# BlinkingLightsW555.net
KiCad netlist of a schematic drawn in EAGLE
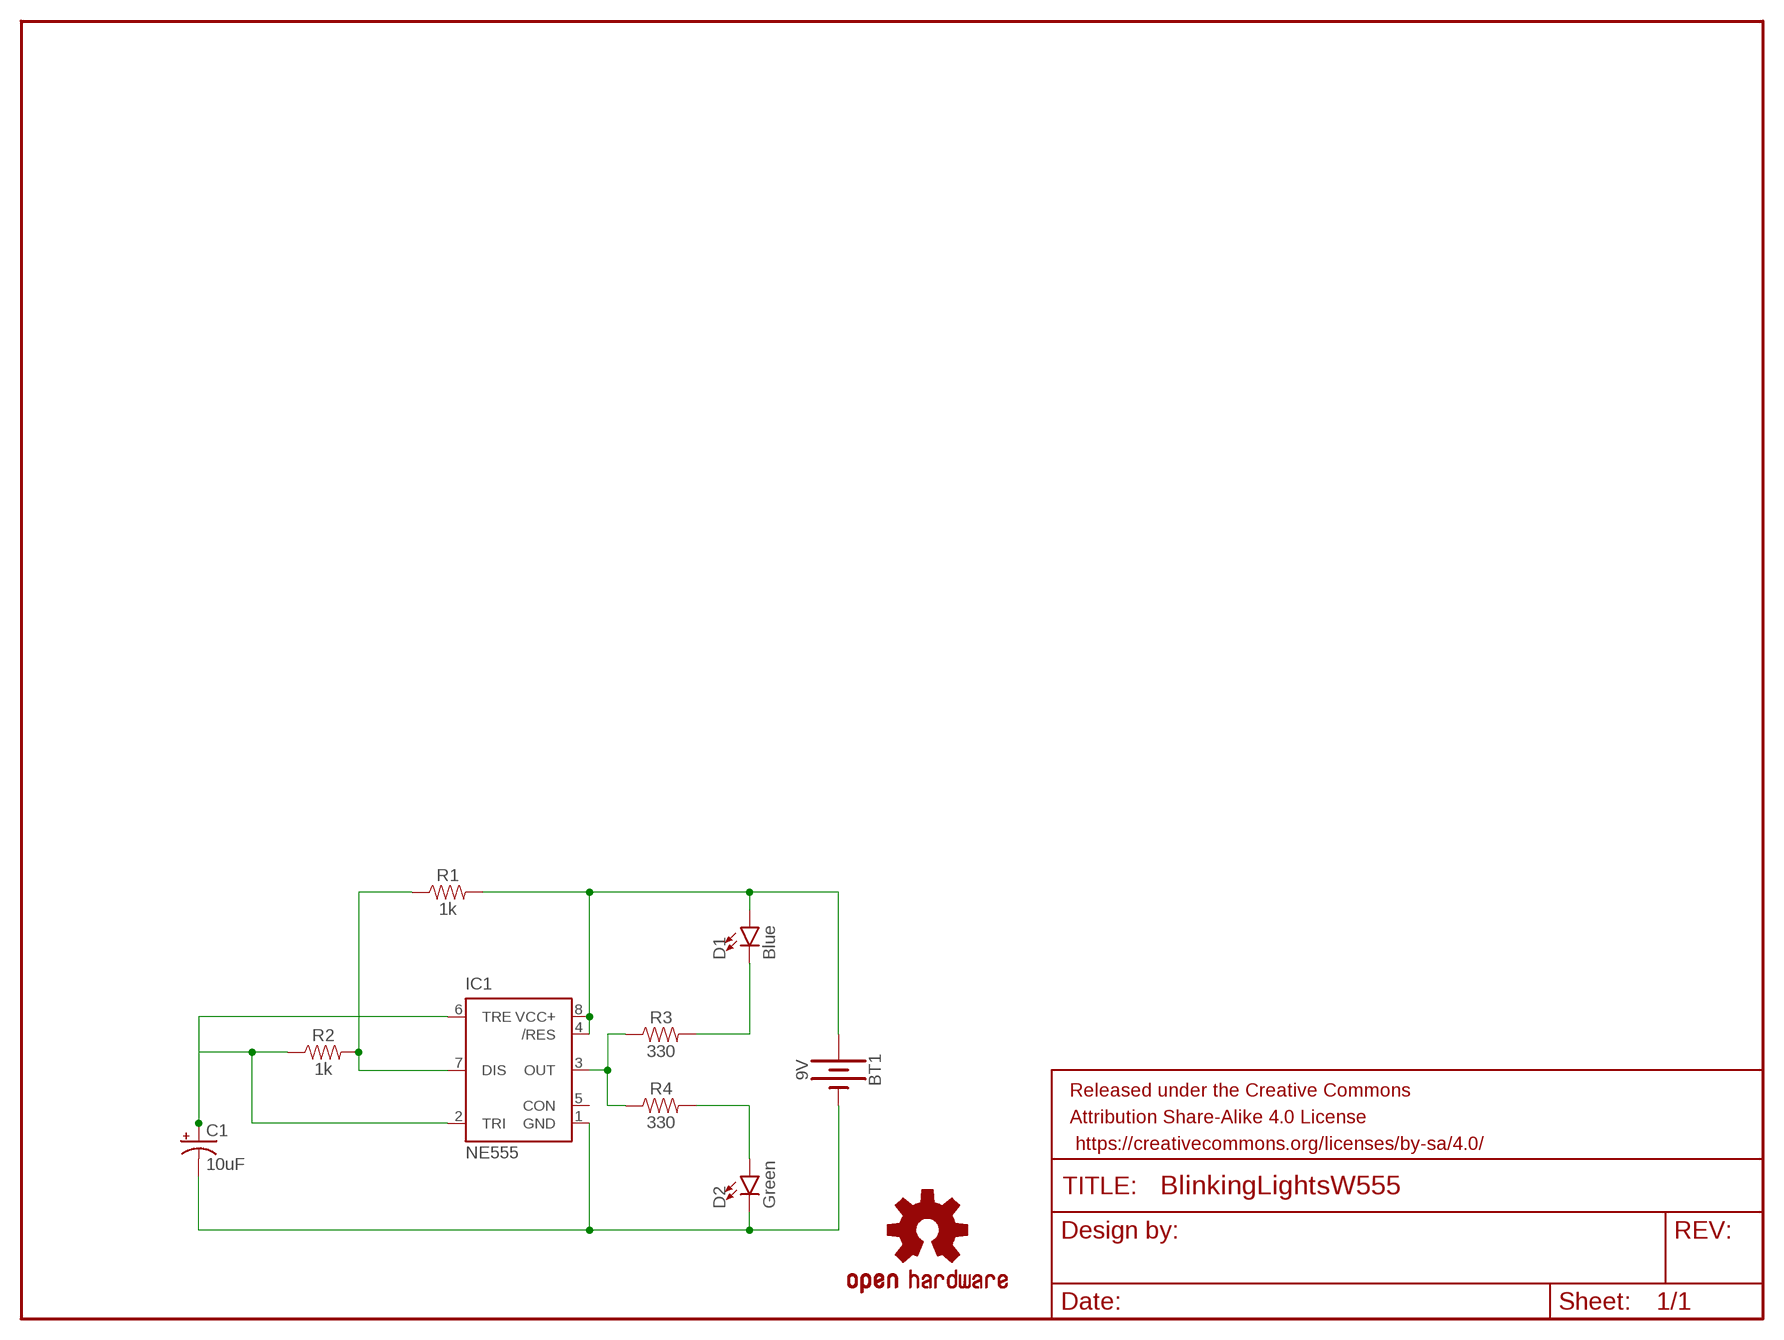
[diagram p0: schematic, sheet 1]

(export (version "E")
  (design (tool "Eeschema 10.0.6"))
  (components
    (comp (ref "BT1")
      (value "9V")
      (footprint "eagle-import:BATTCON_9V")
      (libsource (lib "eagle-import") (part "BATTERY-9V"))
    )
    (comp (ref "C1")
      (value "10uF")
      (footprint "eagle-import:CPOL-RADIAL-2.5MM-5MM-KIT")
      (libsource (lib "eagle-import") (part "10UF-POLAR-RADIAL-2.5MM-KIT-25V-20%"))
    )
    (comp (ref "D1")
      (value "Blue")
      (footprint "eagle-import:LED_10MM")
      (libsource (lib "eagle-import") (part "LED10MM"))
    )
    (comp (ref "D2")
      (value "Green")
      (footprint "eagle-import:LED_10MM")
      (libsource (lib "eagle-import") (part "LED10MM"))
    )
    (comp (ref "FRAME1")
      (value "FRAME-LETTERNO_PACKAGE")
      (footprint "eagle-import:DUMMY")
      (fields (field (name "DESIGNER") "Nobody"))
      (libsource (lib "eagle-import") (part "FRAME-LETTERNO_PACKAGE"))
    )
    (comp (ref "IC1")
      (value "NE555")
      (footprint "eagle-import:DIL-08")
      (fields (field (name "MF") "Arrow Electronics") (field (name "MPN") "NE555N"))
      (libsource (lib "eagle-import") (part "NE555"))
    )
    (comp (ref "LOGO2")
      (value "OSHW-LOGOM")
      (footprint "eagle-import:OSHW-LOGO-M")
      (libsource (lib "eagle-import") (part "OSHW-LOGOM"))
    )
    (comp (ref "R1")
      (value "1k")
      (footprint "eagle-import:AXIAL-0.3")
      (libsource (lib "eagle-import") (part "1KOHM-HORIZ-1/4W-1%"))
    )
    (comp (ref "R2")
      (value "1k")
      (footprint "eagle-import:AXIAL-0.3")
      (libsource (lib "eagle-import") (part "1KOHM-HORIZ-1/4W-1%"))
    )
    (comp (ref "R3")
      (value "330")
      (footprint "eagle-import:AXIAL-0.3")
      (libsource (lib "eagle-import") (part "330OHM-HORIZ-1/10W-5%"))
    )
    (comp (ref "R4")
      (value "330")
      (footprint "eagle-import:AXIAL-0.3")
      (libsource (lib "eagle-import") (part "330OHM-HORIZ-1/10W-5%"))
    )
  )
  (nets
    (net (code "1") (name "Net-(C1-+)") (class "Default")
      (node (ref "C1") (pin "1") (pinfunction "+_1") (pintype "passive"))
      (node (ref "IC1") (pin "2") (pinfunction "TRI_2") (pintype "input"))
      (node (ref "IC1") (pin "6") (pinfunction "TRE_6") (pintype "input"))
      (node (ref "R2") (pin "P$1") (pinfunction "1_P$1") (pintype "passive"))
    )
    (net (code "2") (name "Net-(C1--)") (class "Default")
      (node (ref "BT1") (pin "-") (pinfunction "-_-") (pintype "power_in"))
      (node (ref "C1") (pin "2") (pinfunction "-_2") (pintype "passive"))
      (node (ref "D2") (pin "C") (pinfunction "C_C") (pintype "passive"))
      (node (ref "IC1") (pin "1") (pinfunction "GND_1") (pintype "power_in"))
    )
    (net (code "3") (name "Net-(IC1-DIS)") (class "Default")
      (node (ref "IC1") (pin "7") (pinfunction "DIS_7") (pintype "input"))
      (node (ref "R1") (pin "P$1") (pinfunction "1_P$1") (pintype "passive"))
      (node (ref "R2") (pin "P$2") (pinfunction "2_P$2") (pintype "passive"))
    )
    (net (code "4") (name "Net-(IC1-OUT)") (class "Default")
      (node (ref "IC1") (pin "3") (pinfunction "OUT_3") (pintype "output"))
      (node (ref "R3") (pin "P$1") (pinfunction "1_P$1") (pintype "passive"))
      (node (ref "R4") (pin "P$1") (pinfunction "1_P$1") (pintype "passive"))
    )
    (net (code "5") (name "Net-(IC1-VCC+)") (class "Default")
      (node (ref "BT1") (pin "+") (pinfunction "+_+") (pintype "power_in"))
      (node (ref "D1") (pin "A") (pinfunction "A_A") (pintype "passive"))
      (node (ref "IC1") (pin "4") (pinfunction "/RES_4") (pintype "input"))
      (node (ref "IC1") (pin "8") (pinfunction "VCC+_8") (pintype "power_in"))
      (node (ref "R1") (pin "P$2") (pinfunction "2_P$2") (pintype "passive"))
    )
    (net (code "6") (name "Net-(R3-2)") (class "Default")
      (node (ref "D1") (pin "C") (pinfunction "C_C") (pintype "passive"))
      (node (ref "R3") (pin "P$2") (pinfunction "2_P$2") (pintype "passive"))
    )
    (net (code "7") (name "Net-(R4-2)") (class "Default")
      (node (ref "D2") (pin "A") (pinfunction "A_A") (pintype "passive"))
      (node (ref "R4") (pin "P$2") (pinfunction "2_P$2") (pintype "passive"))
    )
    (net (code "8") (name "unconnected-(IC1-CON-Pad5)") (class "Default")
      (node (ref "IC1") (pin "5") (pinfunction "CON_5") (pintype "input"))
    )
  )
)
